# queso_dip_v49.net
KiCad netlist of a schematic drawn in EAGLE
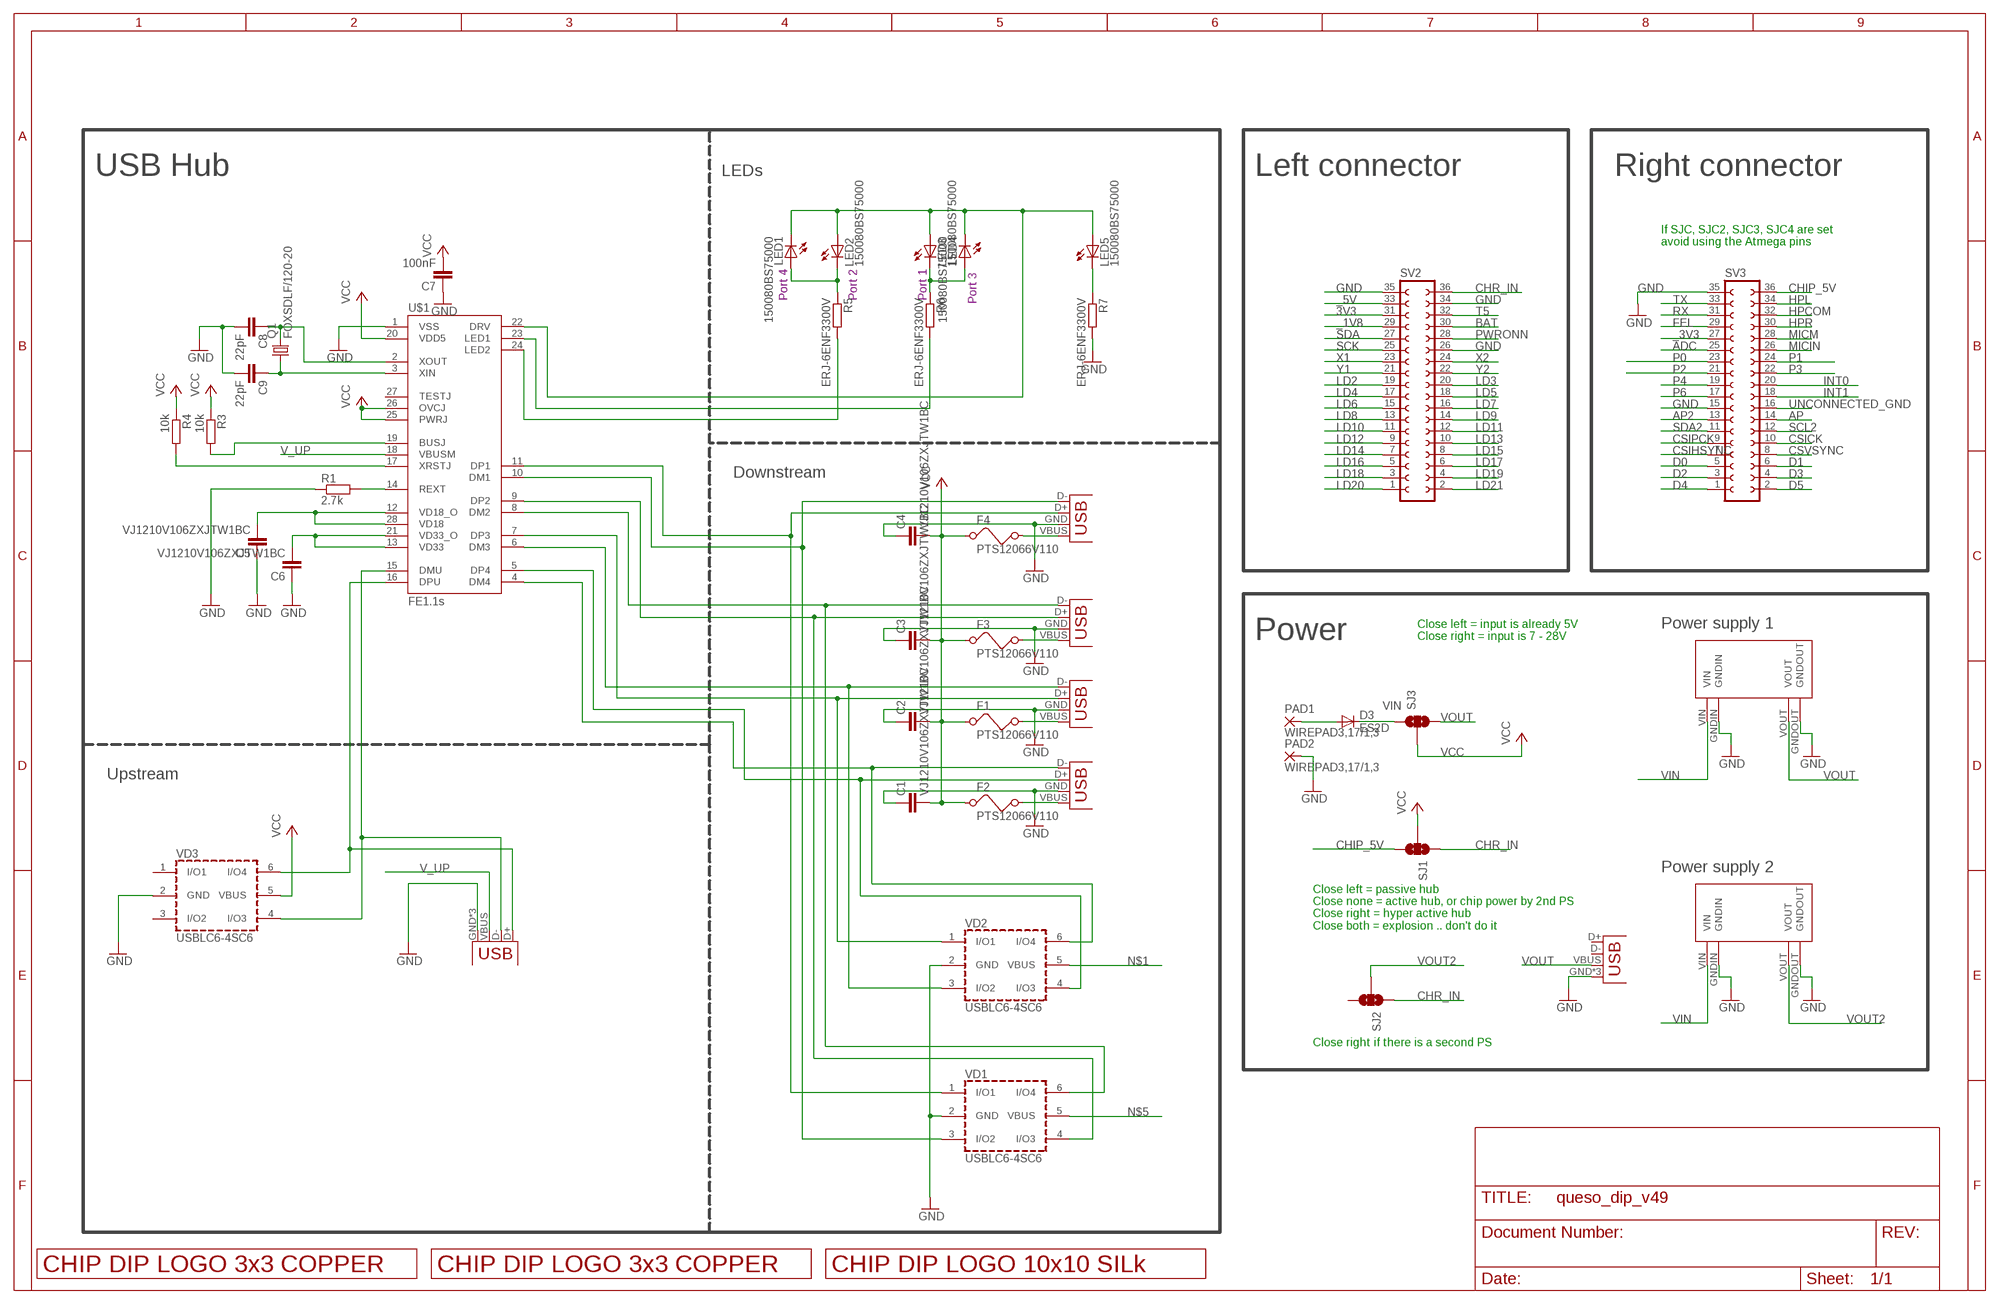
[diagram p0: schematic, sheet 1]

(export (version "E")
  (design (tool "Eeschema 10.0.6"))
  (components
    (comp (ref "C1")
      (value "VJ1210V106ZXJTW1BC")
      (footprint "eagle-import:C1210")
      (libsource (lib "eagle-import") (part "C-EUC1210"))
    )
    (comp (ref "C2")
      (value "VJ1210V106ZXJTW1BC")
      (footprint "eagle-import:C1210")
      (libsource (lib "eagle-import") (part "C-EUC1210"))
    )
    (comp (ref "C3")
      (value "VJ1210V106ZXJTW1BC")
      (footprint "eagle-import:C1210")
      (libsource (lib "eagle-import") (part "C-EUC1210"))
    )
    (comp (ref "C4")
      (value "VJ1210V106ZXJTW1BC")
      (footprint "eagle-import:C1210")
      (libsource (lib "eagle-import") (part "C-EUC1210"))
    )
    (comp (ref "C5")
      (value "VJ1210V106ZXJTW1BC")
      (footprint "eagle-import:C1210")
      (libsource (lib "eagle-import") (part "C-EUC1210"))
    )
    (comp (ref "C6")
      (value "VJ1210V106ZXJTW1BC")
      (footprint "eagle-import:C1210")
      (libsource (lib "eagle-import") (part "C-EUC1210"))
    )
    (comp (ref "C7")
      (value "100nF")
      (footprint "eagle-import:C0805")
      (libsource (lib "eagle-import") (part "C-EUC0805"))
    )
    (comp (ref "C8")
      (value "22pF")
      (footprint "eagle-import:C0805")
      (libsource (lib "eagle-import") (part "C-EUC0805"))
    )
    (comp (ref "C9")
      (value "22pF")
      (footprint "eagle-import:C0805")
      (libsource (lib "eagle-import") (part "C-EUC0805"))
    )
    (comp (ref "D3")
      (value "ES2D")
      (footprint "eagle-import:SMB")
      (libsource (lib "eagle-import") (part "ES2D"))
    )
    (comp (ref "DATA_USB")
      (value "USBUSB-MICROB-SMT-DIP")
      (footprint "eagle-import:USB-MICROB-SMT-DIP")
      (libsource (lib "eagle-import") (part "USBUSB-MICROB-SMT-DIP"))
    )
    (comp (ref "F1")
      (value "PTS12066V110")
      (footprint "eagle-import:1210")
      (libsource (lib "eagle-import") (part "FUSED"))
    )
    (comp (ref "F2")
      (value "PTS12066V110")
      (footprint "eagle-import:1210")
      (libsource (lib "eagle-import") (part "FUSED"))
    )
    (comp (ref "F3")
      (value "PTS12066V110")
      (footprint "eagle-import:1210")
      (libsource (lib "eagle-import") (part "FUSED"))
    )
    (comp (ref "F4")
      (value "PTS12066V110")
      (footprint "eagle-import:1210")
      (libsource (lib "eagle-import") (part "FUSED"))
    )
    (comp (ref "LED1")
      (value "150080BS75000")
      (footprint "eagle-import:CHIP-LED0805")
      (libsource (lib "eagle-import") (part "LEDCHIP-LED0805"))
    )
    (comp (ref "LED2")
      (value "150080BS75000")
      (footprint "eagle-import:CHIP-LED0805")
      (libsource (lib "eagle-import") (part "LEDCHIP-LED0805"))
    )
    (comp (ref "LED3")
      (value "150080BS75000")
      (footprint "eagle-import:CHIP-LED0805")
      (libsource (lib "eagle-import") (part "LEDCHIP-LED0805"))
    )
    (comp (ref "LED4")
      (value "150080BS75000")
      (footprint "eagle-import:CHIP-LED0805")
      (libsource (lib "eagle-import") (part "LEDCHIP-LED0805"))
    )
    (comp (ref "LED5")
      (value "150080BS75000")
      (footprint "eagle-import:CHIP-LED0805")
      (libsource (lib "eagle-import") (part "LEDCHIP-LED0805"))
    )
    (comp (ref "PAD1")
      (value "WIREPAD3,17/1,3")
      (footprint "eagle-import:3,17_1,3")
      (libsource (lib "eagle-import") (part "WIREPAD3,17/1,3"))
    )
    (comp (ref "PAD2")
      (value "WIREPAD3,17/1,3")
      (footprint "eagle-import:3,17_1,3")
      (libsource (lib "eagle-import") (part "WIREPAD3,17/1,3"))
    )
    (comp (ref "POWER_USB")
      (value "USBUSB-MICROB-SMT-DIP")
      (footprint "eagle-import:USB-MICROB-SMT-DIP")
      (libsource (lib "eagle-import") (part "USBUSB-MICROB-SMT-DIP"))
    )
    (comp (ref "Q1")
      (value "FOXSDLF/120-20")
      (footprint "eagle-import:SM49")
      (libsource (lib "eagle-import") (part "CRYSTALSM49"))
    )
    (comp (ref "R1")
      (value "2.7k")
      (footprint "eagle-import:R0805")
      (libsource (lib "eagle-import") (part "R-EU_R0805"))
    )
    (comp (ref "R3")
      (value "10k")
      (footprint "eagle-import:R0805")
      (libsource (lib "eagle-import") (part "R-EU_R0805"))
    )
    (comp (ref "R4")
      (value "10k")
      (footprint "eagle-import:R0805")
      (libsource (lib "eagle-import") (part "R-EU_R0805"))
    )
    (comp (ref "R5")
      (value "ERJ-6ENF3300V")
      (footprint "eagle-import:R0805")
      (libsource (lib "eagle-import") (part "R-EU_R0805"))
    )
    (comp (ref "R6")
      (value "ERJ-6ENF3300V")
      (footprint "eagle-import:R0805")
      (libsource (lib "eagle-import") (part "R-EU_R0805"))
    )
    (comp (ref "R7")
      (value "ERJ-6ENF3300V")
      (footprint "eagle-import:R0805")
      (libsource (lib "eagle-import") (part "R-EU_R0805"))
    )
    (comp (ref "SJ1")
      (value "SOLDERJUMPER_2WAYT")
      (footprint "eagle-import:SJ_2")
      (libsource (lib "eagle-import") (part "SOLDERJUMPER_2WAYT"))
    )
    (comp (ref "SJ2")
      (value "SOLDERJUMPER_2WAYT")
      (footprint "eagle-import:SJ_2")
      (libsource (lib "eagle-import") (part "SOLDERJUMPER_2WAYT"))
    )
    (comp (ref "SJ3")
      (value "SOLDERJUMPER_2WAYT")
      (footprint "eagle-import:SJ_2")
      (libsource (lib "eagle-import") (part "SOLDERJUMPER_2WAYT"))
    )
    (comp (ref "SV2")
      (value "FE18-2")
      (footprint "eagle-import:FE18-2")
      (libsource (lib "eagle-import") (part "FE18-2"))
    )
    (comp (ref "SV3")
      (value "FE18-2")
      (footprint "eagle-import:FE18-2")
      (libsource (lib "eagle-import") (part "FE18-2"))
    )
    (comp (ref "U$1")
      (value "FE1.1S")
      (footprint "eagle-import:FE1.1S_SSOP-28")
      (libsource (lib "eagle-import") (part "FE1.1S"))
    )
    (comp (ref "U$2")
      (value "LOGO_3X3_COPPER")
      (footprint "eagle-import:LOGO_3X3_COPPER")
      (libsource (lib "eagle-import") (part "LOGO_3X3_COPPER"))
    )
    (comp (ref "U$3")
      (value "MP1584EN")
      (footprint "eagle-import:MP1584EN")
      (libsource (lib "eagle-import") (part "MP1584EN"))
    )
    (comp (ref "U$4")
      (value "LOGO_3X3_COPPER")
      (footprint "eagle-import:LOGO_3X3_COPPER")
      (libsource (lib "eagle-import") (part "LOGO_3X3_COPPER"))
    )
    (comp (ref "U$5")
      (value "LOGO_10X10_SILK")
      (footprint "eagle-import:LOGO_10X10_SILK")
      (libsource (lib "eagle-import") (part "LOGO_10X10_SILK"))
    )
    (comp (ref "U$9")
      (value "MP1584EN")
      (footprint "eagle-import:MP1584EN")
      (libsource (lib "eagle-import") (part "MP1584EN"))
    )
    (comp (ref "VD1")
      (value "USBLC6-4SC6")
      (footprint "eagle-import:SOT-23-6L")
      (libsource (lib "eagle-import") (part "USBLC6-4SC6"))
    )
    (comp (ref "VD2")
      (value "USBLC6-4SC6")
      (footprint "eagle-import:SOT-23-6L")
      (libsource (lib "eagle-import") (part "USBLC6-4SC6"))
    )
    (comp (ref "VD3")
      (value "USBLC6-4SC6")
      (footprint "eagle-import:SOT-23-6L")
      (libsource (lib "eagle-import") (part "USBLC6-4SC6"))
    )
    (comp (ref "X1")
      (value "USB-A-HU")
      (footprint "eagle-import:USB-A-HU")
      (libsource (lib "eagle-import") (part "USB-A-HU"))
    )
    (comp (ref "X2")
      (value "USB-A-HU")
      (footprint "eagle-import:USB-A-HU")
      (libsource (lib "eagle-import") (part "USB-A-HU"))
    )
    (comp (ref "X3")
      (value "USB-A-HU")
      (footprint "eagle-import:USB-A-HU")
      (libsource (lib "eagle-import") (part "USB-A-HU"))
    )
    (comp (ref "X4")
      (value "USB-A-HU")
      (footprint "eagle-import:USB-A-HU")
      (libsource (lib "eagle-import") (part "USB-A-HU"))
    )
  )
  (nets
    (net (code "1") (name "/3V3") (class "Default")
      (node (ref "SV2") (pin "31") (pinfunction "31_31") (pintype "passive"))
    )
    (net (code "2") (name "/ADC") (class "Default")
      (node (ref "SV3") (pin "25") (pinfunction "25_25") (pintype "passive"))
    )
    (net (code "3") (name "/AP") (class "Default")
      (node (ref "SV3") (pin "14") (pinfunction "14_14") (pintype "passive"))
    )
    (net (code "4") (name "/AP2") (class "Default")
      (node (ref "SV3") (pin "13") (pinfunction "13_13") (pintype "passive"))
    )
    (net (code "5") (name "/BAT") (class "Default")
      (node (ref "SV2") (pin "30") (pinfunction "30_30") (pintype "passive"))
    )
    (net (code "6") (name "/CHIP_5V") (class "Default")
      (node (ref "SJ1") (pin "3") (pinfunction "3_3") (pintype "passive"))
      (node (ref "SV3") (pin "36") (pinfunction "36_36") (pintype "passive"))
    )
    (net (code "7") (name "/CHR_IN") (class "Default")
      (node (ref "SJ1") (pin "1") (pinfunction "1_1") (pintype "passive"))
      (node (ref "SJ2") (pin "1") (pinfunction "1_1") (pintype "passive"))
      (node (ref "SV2") (pin "36") (pinfunction "36_36") (pintype "passive"))
    )
    (net (code "8") (name "/CSICK") (class "Default")
      (node (ref "SV3") (pin "10") (pinfunction "10_10") (pintype "passive"))
    )
    (net (code "9") (name "/CSIHSYNC") (class "Default")
      (node (ref "SV3") (pin "7") (pinfunction "7_7") (pintype "passive"))
    )
    (net (code "10") (name "/CSIPCK") (class "Default")
      (node (ref "SV3") (pin "9") (pinfunction "9_9") (pintype "passive"))
    )
    (net (code "11") (name "/CSVSYNC") (class "Default")
      (node (ref "SV3") (pin "8") (pinfunction "8_8") (pintype "passive"))
    )
    (net (code "12") (name "/D0") (class "Default")
      (node (ref "SV3") (pin "5") (pinfunction "5_5") (pintype "passive"))
    )
    (net (code "13") (name "/D1") (class "Default")
      (node (ref "SV3") (pin "6") (pinfunction "6_6") (pintype "passive"))
    )
    (net (code "14") (name "/D2") (class "Default")
      (node (ref "SV3") (pin "3") (pinfunction "3_3") (pintype "passive"))
    )
    (net (code "15") (name "/D3") (class "Default")
      (node (ref "SV3") (pin "4") (pinfunction "4_4") (pintype "passive"))
    )
    (net (code "16") (name "/D4") (class "Default")
      (node (ref "SV3") (pin "1") (pinfunction "1_1") (pintype "passive"))
    )
    (net (code "17") (name "/D5") (class "Default")
      (node (ref "SV3") (pin "2") (pinfunction "2_2") (pintype "passive"))
    )
    (net (code "18") (name "/FEL") (class "Default")
      (node (ref "SV3") (pin "29") (pinfunction "29_29") (pintype "passive"))
    )
    (net (code "19") (name "/HPCOM") (class "Default")
      (node (ref "SV3") (pin "32") (pinfunction "32_32") (pintype "passive"))
    )
    (net (code "20") (name "/HPL") (class "Default")
      (node (ref "SV3") (pin "34") (pinfunction "34_34") (pintype "passive"))
    )
    (net (code "21") (name "/HPR") (class "Default")
      (node (ref "SV3") (pin "30") (pinfunction "30_30") (pintype "passive"))
    )
    (net (code "22") (name "/INT0") (class "Default")
      (node (ref "SV3") (pin "20") (pinfunction "20_20") (pintype "passive"))
    )
    (net (code "23") (name "/INT1") (class "Default")
      (node (ref "SV3") (pin "18") (pinfunction "18_18") (pintype "passive"))
    )
    (net (code "24") (name "/LD2") (class "Default")
      (node (ref "SV2") (pin "19") (pinfunction "19_19") (pintype "passive"))
    )
    (net (code "25") (name "/LD3") (class "Default")
      (node (ref "SV2") (pin "20") (pinfunction "20_20") (pintype "passive"))
    )
    (net (code "26") (name "/LD4") (class "Default")
      (node (ref "SV2") (pin "17") (pinfunction "17_17") (pintype "passive"))
    )
    (net (code "27") (name "/LD5") (class "Default")
      (node (ref "SV2") (pin "18") (pinfunction "18_18") (pintype "passive"))
    )
    (net (code "28") (name "/LD6") (class "Default")
      (node (ref "SV2") (pin "15") (pinfunction "15_15") (pintype "passive"))
    )
    (net (code "29") (name "/LD7") (class "Default")
      (node (ref "SV2") (pin "16") (pinfunction "16_16") (pintype "passive"))
    )
    (net (code "30") (name "/LD8") (class "Default")
      (node (ref "SV2") (pin "13") (pinfunction "13_13") (pintype "passive"))
    )
    (net (code "31") (name "/LD9") (class "Default")
      (node (ref "SV2") (pin "14") (pinfunction "14_14") (pintype "passive"))
    )
    (net (code "32") (name "/LD10") (class "Default")
      (node (ref "SV2") (pin "11") (pinfunction "11_11") (pintype "passive"))
    )
    (net (code "33") (name "/LD11") (class "Default")
      (node (ref "SV2") (pin "12") (pinfunction "12_12") (pintype "passive"))
    )
    (net (code "34") (name "/LD12") (class "Default")
      (node (ref "SV2") (pin "9") (pinfunction "9_9") (pintype "passive"))
    )
    (net (code "35") (name "/LD13") (class "Default")
      (node (ref "SV2") (pin "10") (pinfunction "10_10") (pintype "passive"))
    )
    (net (code "36") (name "/LD14") (class "Default")
      (node (ref "SV2") (pin "7") (pinfunction "7_7") (pintype "passive"))
    )
    (net (code "37") (name "/LD15") (class "Default")
      (node (ref "SV2") (pin "8") (pinfunction "8_8") (pintype "passive"))
    )
    (net (code "38") (name "/LD16") (class "Default")
      (node (ref "SV2") (pin "5") (pinfunction "5_5") (pintype "passive"))
    )
    (net (code "39") (name "/LD17") (class "Default")
      (node (ref "SV2") (pin "6") (pinfunction "6_6") (pintype "passive"))
    )
    (net (code "40") (name "/LD18") (class "Default")
      (node (ref "SV2") (pin "3") (pinfunction "3_3") (pintype "passive"))
    )
    (net (code "41") (name "/LD19") (class "Default")
      (node (ref "SV2") (pin "4") (pinfunction "4_4") (pintype "passive"))
    )
    (net (code "42") (name "/LD20") (class "Default")
      (node (ref "SV2") (pin "1") (pinfunction "1_1") (pintype "passive"))
    )
    (net (code "43") (name "/LD21") (class "Default")
      (node (ref "SV2") (pin "2") (pinfunction "2_2") (pintype "passive"))
    )
    (net (code "44") (name "/MICIN") (class "Default")
      (node (ref "SV3") (pin "26") (pinfunction "26_26") (pintype "passive"))
    )
    (net (code "45") (name "/MICM") (class "Default")
      (node (ref "SV3") (pin "28") (pinfunction "28_28") (pintype "passive"))
    )
    (net (code "46") (name "/N$1") (class "Default")
      (node (ref "F2") (pin "2") (pinfunction "2_2") (pintype "passive"))
      (node (ref "VD2") (pin "5") (pinfunction "VBUS_5") (pintype "bidirectional"))
      (node (ref "X1") (pin "VBUS") (pinfunction "GND_VBUS") (pintype "bidirectional"))
    )
    (net (code "47") (name "/N$5") (class "Default")
      (node (ref "F3") (pin "2") (pinfunction "2_2") (pintype "passive"))
      (node (ref "VD1") (pin "5") (pinfunction "VBUS_5") (pintype "bidirectional"))
      (node (ref "X3") (pin "VBUS") (pinfunction "GND_VBUS") (pintype "bidirectional"))
    )
    (net (code "48") (name "/P0") (class "Default")
      (node (ref "SV3") (pin "23") (pinfunction "23_23") (pintype "passive"))
    )
    (net (code "49") (name "/P1") (class "Default")
      (node (ref "SV3") (pin "24") (pinfunction "24_24") (pintype "passive"))
    )
    (net (code "50") (name "/P2") (class "Default")
      (node (ref "SV3") (pin "21") (pinfunction "21_21") (pintype "passive"))
    )
    (net (code "51") (name "/P3") (class "Default")
      (node (ref "SV3") (pin "22") (pinfunction "22_22") (pintype "passive"))
    )
    (net (code "52") (name "/P4") (class "Default")
      (node (ref "SV3") (pin "19") (pinfunction "19_19") (pintype "passive"))
    )
    (net (code "53") (name "/P6") (class "Default")
      (node (ref "SV3") (pin "17") (pinfunction "17_17") (pintype "passive"))
    )
    (net (code "54") (name "/PWRONN") (class "Default")
      (node (ref "SV2") (pin "28") (pinfunction "28_28") (pintype "passive"))
    )
    (net (code "55") (name "/RX") (class "Default")
      (node (ref "SV3") (pin "31") (pinfunction "31_31") (pintype "passive"))
    )
    (net (code "56") (name "/SCK") (class "Default")
      (node (ref "SV2") (pin "25") (pinfunction "25_25") (pintype "passive"))
    )
    (net (code "57") (name "/SCL2") (class "Default")
      (node (ref "SV3") (pin "12") (pinfunction "12_12") (pintype "passive"))
    )
    (net (code "58") (name "/SDA") (class "Default")
      (node (ref "SV2") (pin "27") (pinfunction "27_27") (pintype "passive"))
    )
    (net (code "59") (name "/SDA2") (class "Default")
      (node (ref "SV3") (pin "11") (pinfunction "11_11") (pintype "passive"))
    )
    (net (code "60") (name "/T5") (class "Default")
      (node (ref "SV2") (pin "32") (pinfunction "32_32") (pintype "passive"))
    )
    (net (code "61") (name "/TX") (class "Default")
      (node (ref "SV3") (pin "33") (pinfunction "33_33") (pintype "passive"))
    )
    (net (code "62") (name "/UNCONNECTED_GND") (class "Default")
      (node (ref "SV3") (pin "16") (pinfunction "16_16") (pintype "passive"))
    )
    (net (code "63") (name "/VIN") (class "Default")
      (node (ref "D3") (pin "C") (pinfunction "C_C") (pintype "passive"))
      (node (ref "SJ3") (pin "1") (pinfunction "1_1") (pintype "passive"))
      (node (ref "U$3") (pin "VIN") (pinfunction "VIN_VIN") (pintype "power_in"))
      (node (ref "U$9") (pin "VIN") (pinfunction "VIN_VIN") (pintype "power_in"))
    )
    (net (code "64") (name "/VOUT") (class "Default")
      (node (ref "POWER_USB") (pin "VBUS") (pinfunction "VBUS_VBUS") (pintype "bidirectional"))
      (node (ref "SJ3") (pin "3") (pinfunction "3_3") (pintype "passive"))
      (node (ref "U$9") (pin "VOUT") (pinfunction "VOUT_VOUT") (pintype "power_in"))
    )
    (net (code "65") (name "/VOUT2") (class "Default")
      (node (ref "SJ2") (pin "2") (pinfunction "2_2") (pintype "passive"))
      (node (ref "U$3") (pin "VOUT") (pinfunction "VOUT_VOUT") (pintype "power_in"))
    )
    (net (code "66") (name "/V_UP") (class "Default")
      (node (ref "DATA_USB") (pin "VBUS") (pinfunction "VBUS_VBUS") (pintype "bidirectional"))
      (node (ref "U$1") (pin "18") (pinfunction "VBUSM_18") (pintype "bidirectional"))
    )
    (net (code "67") (name "/X1") (class "Default")
      (node (ref "SV2") (pin "23") (pinfunction "23_23") (pintype "passive"))
    )
    (net (code "68") (name "/X2") (class "Default")
      (node (ref "SV2") (pin "24") (pinfunction "24_24") (pintype "passive"))
    )
    (net (code "69") (name "/Y1") (class "Default")
      (node (ref "SV2") (pin "21") (pinfunction "21_21") (pintype "passive"))
    )
    (net (code "70") (name "/Y2") (class "Default")
      (node (ref "SV2") (pin "22") (pinfunction "22_22") (pintype "passive"))
    )
    (net (code "71") (name "/_1V8") (class "Default")
      (node (ref "SV2") (pin "29") (pinfunction "29_29") (pintype "passive"))
    )
    (net (code "72") (name "/_3V3") (class "Default")
      (node (ref "SV3") (pin "27") (pinfunction "27_27") (pintype "passive"))
    )
    (net (code "73") (name "/_5V") (class "Default")
      (node (ref "SV2") (pin "33") (pinfunction "33_33") (pintype "passive"))
    )
    (net (code "74") (name "GND") (class "Default")
      (node (ref "C1") (pin "1") (pinfunction "1_1") (pintype "passive"))
      (node (ref "C2") (pin "1") (pinfunction "1_1") (pintype "passive"))
      (node (ref "C3") (pin "1") (pinfunction "1_1") (pintype "passive"))
      (node (ref "C4") (pin "1") (pinfunction "1_1") (pintype "passive"))
      (node (ref "C5") (pin "1") (pinfunction "1_1") (pintype "passive"))
      (node (ref "C6") (pin "1") (pinfunction "1_1") (pintype "passive"))
      (node (ref "C7") (pin "1") (pinfunction "1_1") (pintype "passive"))
      (node (ref "C8") (pin "2") (pinfunction "2_2") (pintype "passive"))
      (node (ref "C9") (pin "2") (pinfunction "2_2") (pintype "passive"))
      (node (ref "DATA_USB") (pin "GND") (pinfunction "GND_GND") (pintype "bidirectional"))
      (node (ref "DATA_USB") (pin "MT1") (pinfunction "GND_MT1") (pintype "bidirectional"))
      (node (ref "DATA_USB") (pin "MT2") (pinfunction "GND_MT2") (pintype "bidirectional"))
      (node (ref "PAD2") (pin "1") (pinfunction "P_1") (pintype "passive"))
      (node (ref "POWER_USB") (pin "GND") (pinfunction "GND_GND") (pintype "bidirectional"))
      (node (ref "POWER_USB") (pin "MT1") (pinfunction "GND_MT1") (pintype "bidirectional"))
      (node (ref "POWER_USB") (pin "MT2") (pinfunction "GND_MT2") (pintype "bidirectional"))
      (node (ref "R1") (pin "1") (pinfunction "1_1") (pintype "passive"))
      (node (ref "R7") (pin "2") (pinfunction "2_2") (pintype "passive"))
      (node (ref "SV2") (pin "26") (pinfunction "26_26") (pintype "passive"))
      (node (ref "SV2") (pin "34") (pinfunction "34_34") (pintype "passive"))
      (node (ref "SV2") (pin "35") (pinfunction "35_35") (pintype "passive"))
      (node (ref "SV3") (pin "15") (pinfunction "15_15") (pintype "passive"))
      (node (ref "SV3") (pin "35") (pinfunction "35_35") (pintype "passive"))
      (node (ref "U$1") (pin "1") (pinfunction "VSS_1") (pintype "bidirectional"))
      (node (ref "U$3") (pin "GNDIN") (pinfunction "GNDIN_GNDIN") (pintype "power_in"))
      (node (ref "U$3") (pin "GNDOUT") (pinfunction "GNDOUT_GNDOUT") (pintype "power_in"))
      (node (ref "U$9") (pin "GNDIN") (pinfunction "GNDIN_GNDIN") (pintype "power_in"))
      (node (ref "U$9") (pin "GNDOUT") (pinfunction "GNDOUT_GNDOUT") (pintype "power_in"))
      (node (ref "VD1") (pin "2") (pinfunction "GND_2") (pintype "bidirectional"))
      (node (ref "VD2") (pin "2") (pinfunction "GND_2") (pintype "bidirectional"))
      (node (ref "VD3") (pin "2") (pinfunction "GND_2") (pintype "bidirectional"))
      (node (ref "X1") (pin "GND") (pinfunction "VBUS_GND") (pintype "bidirectional"))
      (node (ref "X2") (pin "GND") (pinfunction "VBUS_GND") (pintype "bidirectional"))
      (node (ref "X3") (pin "GND") (pinfunction "VBUS_GND") (pintype "bidirectional"))
      (node (ref "X4") (pin "GND") (pinfunction "VBUS_GND") (pintype "bidirectional"))
    )
    (net (code "75") (name "Net-(LED1-PadA)") (class "Default")
      (node (ref "LED1") (pin "A") (pinfunction "A_A") (pintype "passive"))
      (node (ref "LED2") (pin "C") (pinfunction "C_C") (pintype "passive"))
      (node (ref "R5") (pin "1") (pinfunction "1_1") (pintype "passive"))
    )
    (net (code "76") (name "Net-(LED3-PadC)") (class "Default")
      (node (ref "LED3") (pin "C") (pinfunction "C_C") (pintype "passive"))
      (node (ref "LED4") (pin "A") (pinfunction "A_A") (pintype "passive"))
      (node (ref "R6") (pin "1") (pinfunction "1_1") (pintype "passive"))
    )
    (net (code "77") (name "Net-(LED5-PadC)") (class "Default")
      (node (ref "LED5") (pin "C") (pinfunction "C_C") (pintype "passive"))
      (node (ref "R7") (pin "1") (pinfunction "1_1") (pintype "passive"))
    )
    (net (code "78") (name "Net-(PAD1-P)") (class "Default")
      (node (ref "D3") (pin "A") (pinfunction "A_A") (pintype "passive"))
      (node (ref "PAD1") (pin "1") (pinfunction "P_1") (pintype "passive"))
    )
    (net (code "79") (name "Net-(U$1-BUSJ)") (class "Default")
      (node (ref "R3") (pin "2") (pinfunction "2_2") (pintype "passive"))
      (node (ref "U$1") (pin "19") (pinfunction "BUSJ_19") (pintype "bidirectional"))
    )
    (net (code "80") (name "Net-(U$1-DM1)") (class "Default")
      (node (ref "U$1") (pin "10") (pinfunction "DM1_10") (pintype "bidirectional"))
      (node (ref "VD1") (pin "3") (pinfunction "I/O2_3") (pintype "bidirectional"))
      (node (ref "X4") (pin "D-") (pinfunction "D+_D-") (pintype "bidirectional"))
    )
    (net (code "81") (name "Net-(U$1-DM2)") (class "Default")
      (node (ref "U$1") (pin "8") (pinfunction "DM2_8") (pintype "bidirectional"))
      (node (ref "VD1") (pin "6") (pinfunction "I/O4_6") (pintype "bidirectional"))
      (node (ref "X3") (pin "D-") (pinfunction "D+_D-") (pintype "bidirectional"))
    )
    (net (code "82") (name "Net-(U$1-DM3)") (class "Default")
      (node (ref "U$1") (pin "6") (pinfunction "DM3_6") (pintype "bidirectional"))
      (node (ref "VD2") (pin "3") (pinfunction "I/O2_3") (pintype "bidirectional"))
      (node (ref "X2") (pin "D-") (pinfunction "D+_D-") (pintype "bidirectional"))
    )
    (net (code "83") (name "Net-(U$1-DM4)") (class "Default")
      (node (ref "U$1") (pin "4") (pinfunction "DM4_4") (pintype "bidirectional"))
      (node (ref "VD2") (pin "6") (pinfunction "I/O4_6") (pintype "bidirectional"))
      (node (ref "X1") (pin "D-") (pinfunction "D+_D-") (pintype "bidirectional"))
    )
    (net (code "84") (name "Net-(U$1-DMU)") (class "Default")
      (node (ref "DATA_USB") (pin "D-") (pinfunction "D-_D-") (pintype "bidirectional"))
      (node (ref "U$1") (pin "15") (pinfunction "DMU_15") (pintype "bidirectional"))
      (node (ref "VD3") (pin "4") (pinfunction "I/O3_4") (pintype "bidirectional"))
    )
    (net (code "85") (name "Net-(U$1-DP1)") (class "Default")
      (node (ref "U$1") (pin "11") (pinfunction "DP1_11") (pintype "bidirectional"))
      (node (ref "VD1") (pin "1") (pinfunction "I/O1_1") (pintype "bidirectional"))
      (node (ref "X4") (pin "D+") (pinfunction "D-_D+") (pintype "bidirectional"))
    )
    (net (code "86") (name "Net-(U$1-DP2)") (class "Default")
      (node (ref "U$1") (pin "9") (pinfunction "DP2_9") (pintype "bidirectional"))
      (node (ref "VD1") (pin "4") (pinfunction "I/O3_4") (pintype "bidirectional"))
      (node (ref "X3") (pin "D+") (pinfunction "D-_D+") (pintype "bidirectional"))
    )
    (net (code "87") (name "Net-(U$1-DP3)") (class "Default")
      (node (ref "U$1") (pin "7") (pinfunction "DP3_7") (pintype "bidirectional"))
      (node (ref "VD2") (pin "1") (pinfunction "I/O1_1") (pintype "bidirectional"))
      (node (ref "X2") (pin "D+") (pinfunction "D-_D+") (pintype "bidirectional"))
    )
    (net (code "88") (name "Net-(U$1-DP4)") (class "Default")
      (node (ref "U$1") (pin "5") (pinfunction "DP4_5") (pintype "bidirectional"))
      (node (ref "VD2") (pin "4") (pinfunction "I/O3_4") (pintype "bidirectional"))
      (node (ref "X1") (pin "D+") (pinfunction "D-_D+") (pintype "bidirectional"))
    )
    (net (code "89") (name "Net-(U$1-DPU)") (class "Default")
      (node (ref "DATA_USB") (pin "D+") (pinfunction "D+_D+") (pintype "bidirectional"))
      (node (ref "U$1") (pin "16") (pinfunction "DPU_16") (pintype "bidirectional"))
      (node (ref "VD3") (pin "6") (pinfunction "I/O4_6") (pintype "bidirectional"))
    )
    (net (code "90") (name "Net-(U$1-DRV)") (class "Default")
      (node (ref "LED1") (pin "C") (pinfunction "C_C") (pintype "passive"))
      (node (ref "LED2") (pin "A") (pinfunction "A_A") (pintype "passive"))
      (node (ref "LED3") (pin "A") (pinfunction "A_A") (pintype "passive"))
      (node (ref "LED4") (pin "C") (pinfunction "C_C") (pintype "passive"))
      (node (ref "LED5") (pin "A") (pinfunction "A_A") (pintype "passive"))
      (node (ref "U$1") (pin "22") (pinfunction "DRV_22") (pintype "bidirectional"))
    )
    (net (code "91") (name "Net-(U$1-LED1)") (class "Default")
      (node (ref "R6") (pin "2") (pinfunction "2_2") (pintype "passive"))
      (node (ref "U$1") (pin "23") (pinfunction "LED1_23") (pintype "bidirectional"))
    )
    (net (code "92") (name "Net-(U$1-LED2)") (class "Default")
      (node (ref "R5") (pin "2") (pinfunction "2_2") (pintype "passive"))
      (node (ref "U$1") (pin "24") (pinfunction "LED2_24") (pintype "bidirectional"))
    )
    (net (code "93") (name "Net-(U$1-REXT)") (class "Default")
      (node (ref "R1") (pin "2") (pinfunction "2_2") (pintype "passive"))
      (node (ref "U$1") (pin "14") (pinfunction "REXT_14") (pintype "bidirectional"))
    )
    (net (code "94") (name "Net-(U$1-VD18)") (class "Default")
      (node (ref "C5") (pin "2") (pinfunction "2_2") (pintype "passive"))
      (node (ref "U$1") (pin "12") (pinfunction "VD18_O_12") (pintype "bidirectional"))
      (node (ref "U$1") (pin "28") (pinfunction "VD18_28") (pintype "bidirectional"))
    )
    (net (code "95") (name "Net-(U$1-VD33)") (class "Default")
      (node (ref "C6") (pin "2") (pinfunction "2_2") (pintype "passive"))
      (node (ref "U$1") (pin "13") (pinfunction "VD33_13") (pintype "bidirectional"))
      (node (ref "U$1") (pin "21") (pinfunction "VD33_O_21") (pintype "bidirectional"))
    )
    (net (code "96") (name "Net-(U$1-XIN)") (class "Default")
      (node (ref "C9") (pin "1") (pinfunction "1_1") (pintype "passive"))
      (node (ref "Q1") (pin "1") (pinfunction "1_1") (pintype "passive"))
      (node (ref "U$1") (pin "3") (pinfunction "XIN_3") (pintype "bidirectional"))
    )
    (net (code "97") (name "Net-(U$1-XOUT)") (class "Default")
      (node (ref "C8") (pin "1") (pinfunction "1_1") (pintype "passive"))
      (node (ref "Q1") (pin "2") (pinfunction "2_2") (pintype "passive"))
      (node (ref "U$1") (pin "2") (pinfunction "XOUT_2") (pintype "bidirectional"))
    )
    (net (code "98") (name "Net-(U$1-XRSTJ)") (class "Default")
      (node (ref "R4") (pin "2") (pinfunction "2_2") (pintype "passive"))
      (node (ref "U$1") (pin "17") (pinfunction "XRSTJ_17") (pintype "bidirectional"))
    )
    (net (code "99") (name "Net-(X2-GND)") (class "Default")
      (node (ref "F1") (pin "2") (pinfunction "2_2") (pintype "passive"))
      (node (ref "X2") (pin "VBUS") (pinfunction "GND_VBUS") (pintype "bidirectional"))
    )
    (net (code "100") (name "Net-(X4-GND)") (class "Default")
      (node (ref "F4") (pin "2") (pinfunction "2_2") (pintype "passive"))
      (node (ref "X4") (pin "VBUS") (pinfunction "GND_VBUS") (pintype "bidirectional"))
    )
    (net (code "101") (name "VCC") (class "Default")
      (node (ref "C1") (pin "2") (pinfunction "2_2") (pintype "passive"))
      (node (ref "C2") (pin "2") (pinfunction "2_2") (pintype "passive"))
      (node (ref "C3") (pin "2") (pinfunction "2_2") (pintype "passive"))
      (node (ref "C4") (pin "2") (pinfunction "2_2") (pintype "passive"))
      (node (ref "C7") (pin "2") (pinfunction "2_2") (pintype "passive"))
      (node (ref "F1") (pin "1") (pinfunction "1_1") (pintype "passive"))
      (node (ref "F2") (pin "1") (pinfunction "1_1") (pintype "passive"))
      (node (ref "F3") (pin "1") (pinfunction "1_1") (pintype "passive"))
      (node (ref "F4") (pin "1") (pinfunction "1_1") (pintype "passive"))
      (node (ref "R3") (pin "1") (pinfunction "1_1") (pintype "passive"))
      (node (ref "R4") (pin "1") (pinfunction "1_1") (pintype "passive"))
      (node (ref "SJ1") (pin "2") (pinfunction "2_2") (pintype "passive"))
      (node (ref "SJ3") (pin "2") (pinfunction "2_2") (pintype "passive"))
      (node (ref "U$1") (pin "20") (pinfunction "VDD5_20") (pintype "bidirectional"))
      (node (ref "U$1") (pin "25") (pinfunction "PWRJ_25") (pintype "bidirectional"))
      (node (ref "U$1") (pin "26") (pinfunction "OVCJ_26") (pintype "bidirectional"))
      (node (ref "VD3") (pin "5") (pinfunction "VBUS_5") (pintype "bidirectional"))
    )
    (net (code "102") (name "unconnected-(POWER_USB-PadD+)") (class "Default")
      (node (ref "POWER_USB") (pin "D+") (pinfunction "D+_D+") (pintype "bidirectional"))
    )
    (net (code "103") (name "unconnected-(POWER_USB-PadD-)") (class "Default")
      (node (ref "POWER_USB") (pin "D-") (pinfunction "D-_D-") (pintype "bidirectional"))
    )
    (net (code "104") (name "unconnected-(SJ2-Pad3)") (class "Default")
      (node (ref "SJ2") (pin "3") (pinfunction "3_3") (pintype "passive"))
    )
    (net (code "105") (name "unconnected-(U$1-TESTJ-Pad27)") (class "Default")
      (node (ref "U$1") (pin "27") (pinfunction "TESTJ_27") (pintype "bidirectional"))
    )
    (net (code "106") (name "unconnected-(VD3-I{slash}O1-Pad1)") (class "Default")
      (node (ref "VD3") (pin "1") (pinfunction "I/O1_1") (pintype "bidirectional"))
    )
    (net (code "107") (name "unconnected-(VD3-I{slash}O2-Pad3)") (class "Default")
      (node (ref "VD3") (pin "3") (pinfunction "I/O2_3") (pintype "bidirectional"))
    )
  )
)
